# tricorder-teensy-mk-1_0.net
KiCad netlist of a schematic drawn in EAGLE
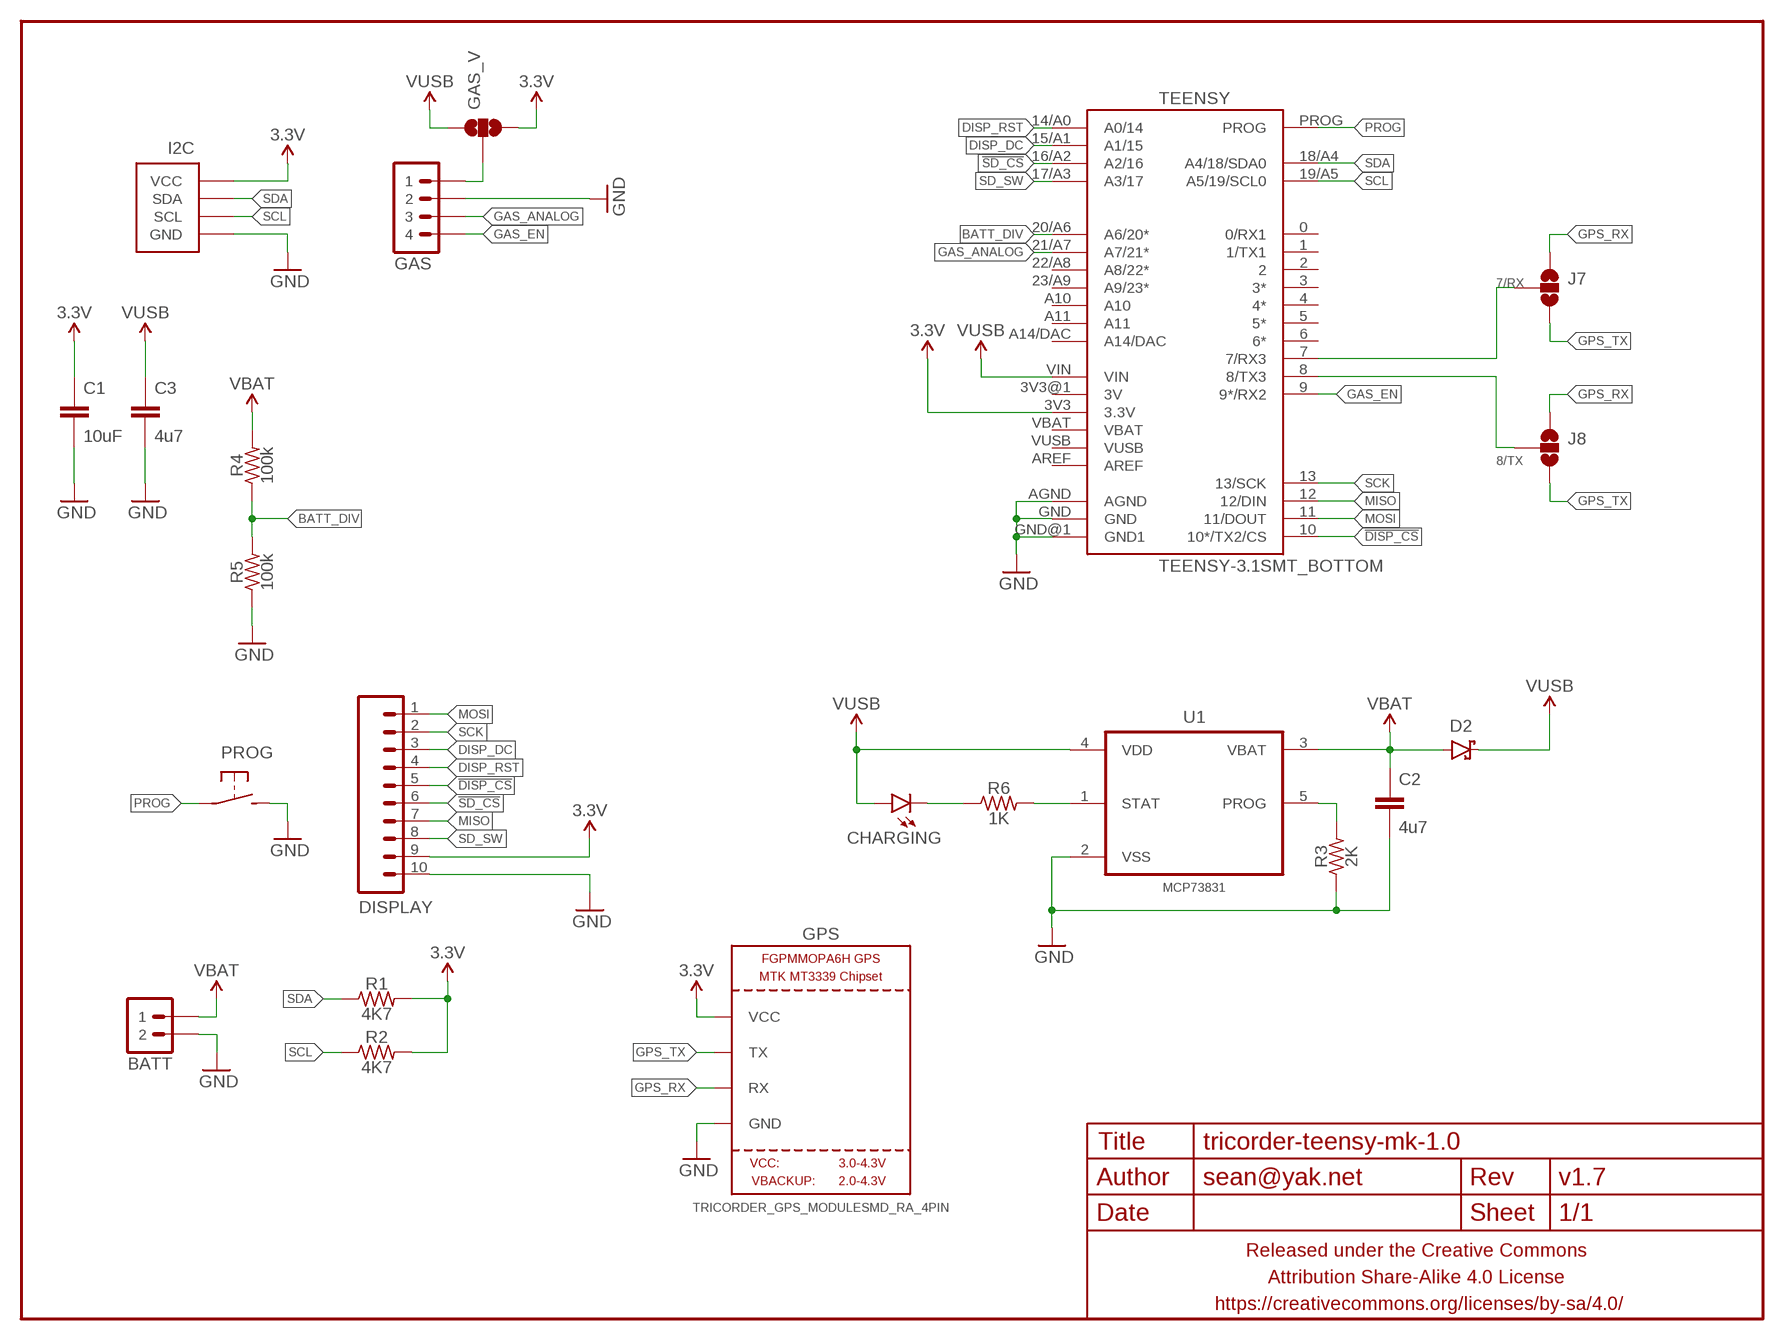
[diagram p0: schematic, sheet 1]

(export (version "E")
  (design (tool "Eeschema 10.0.6"))
  (components
    (comp (ref "BATT")
      (value "M02JST-2MM-SMT")
      (footprint "eagle-import:JST-2-SMD")
      (libsource (lib "eagle-import") (part "M02JST-2MM-SMT"))
    )
    (comp (ref "C1")
      (value "10uF")
      (footprint "eagle-import:C0805-TIGHTER")
      (libsource (lib "eagle-import") (part "CAPACITOR-CERAMICC0805-TIGHTER"))
    )
    (comp (ref "C2")
      (value "4u7")
      (footprint "eagle-import:C0603-TIGHTER")
      (libsource (lib "eagle-import") (part "CAPACITOR-CERAMICC0603-TIGHTER"))
    )
    (comp (ref "C3")
      (value "4u7")
      (footprint "eagle-import:C0603-TIGHTER")
      (libsource (lib "eagle-import") (part "CAPACITOR-CERAMICC0603-TIGHTER"))
    )
    (comp (ref "CHARGING")
      (value "LED0603-TIGHT")
      (footprint "eagle-import:LED-0603-TIGHT")
      (libsource (lib "eagle-import") (part "LED0603-TIGHT"))
    )
    (comp (ref "D2")
      (value "DIODE-SCHOTTKYSOD323")
      (footprint "eagle-import:SOD323-SCHOTTKY")
      (libsource (lib "eagle-import") (part "DIODE-SCHOTTKYSOD323"))
    )
    (comp (ref "DISPLAY")
      (value "M10SMD_RA_2MM")
      (footprint "eagle-import:1X10_SMD_RA_MALE")
      (libsource (lib "eagle-import") (part "M10SMD_RA_2MM"))
    )
    (comp (ref "FRAME1")
      (value "FRAME-LETTERNO_PACKAGE")
      (footprint "eagle-import:DUMMY")
      (fields (field (name "DESIGNER") "sean@yak.net") (field (name "VERSION") "v1.7"))
      (libsource (lib "eagle-import") (part "FRAME-LETTERNO_PACKAGE"))
    )
    (comp (ref "GAS")
      (value "M04SMD_RA_2MM")
      (footprint "eagle-import:1X04_SMD_RA_2MM")
      (libsource (lib "eagle-import") (part "M04SMD_RA_2MM"))
    )
    (comp (ref "GAS_V")
      (value "JUMPER-PAD-3-NOFULL_BOX_SILK")
      (footprint "eagle-import:PAD-JUMPER-3-NO_YES_SILK_FULL_BOX")
      (libsource (lib "eagle-import") (part "JUMPER-PAD-3-NOFULL_BOX_SILK"))
    )
    (comp (ref "GPS")
      (value "TRICORDER_GPS_MODULESMD_RA_4PIN")
      (footprint "eagle-import:TRICORDER_GPS_MODULE_RA_CONN_SMD_4PIN")
      (libsource (lib "eagle-import") (part "TRICORDER_GPS_MODULESMD_RA_4PIN"))
    )
    (comp (ref "I2C")
      (value "M04-I2CSMD_2MM_RA")
      (footprint "eagle-import:1X04_SMD_RA_2MM_I2C")
      (libsource (lib "eagle-import") (part "M04-I2CSMD_2MM_RA"))
    )
    (comp (ref "J7")
      (value "JUMPER-PAD-3-NOFULL_BOX_SILK")
      (footprint "eagle-import:PAD-JUMPER-3-NO_YES_SILK_FULL_BOX")
      (libsource (lib "eagle-import") (part "JUMPER-PAD-3-NOFULL_BOX_SILK"))
    )
    (comp (ref "J8")
      (value "JUMPER-PAD-3-NOFULL_BOX_SILK")
      (footprint "eagle-import:PAD-JUMPER-3-NO_YES_SILK_FULL_BOX")
      (libsource (lib "eagle-import") (part "JUMPER-PAD-3-NOFULL_BOX_SILK"))
    )
    (comp (ref "PROG")
      (value "SPST-NO-TACTCK-PTS840-GK")
      (footprint "eagle-import:TACTILE-SMD-CK-PTS840-GK")
      (libsource (lib "eagle-import") (part "SPST-NO-TACTCK-PTS840-GK"))
    )
    (comp (ref "R1")
      (value "4K7")
      (footprint "eagle-import:R0603-TIGHTER")
      (libsource (lib "eagle-import") (part "RESISTORR0603-TIGHTER"))
    )
    (comp (ref "R2")
      (value "4K7")
      (footprint "eagle-import:R0603-TIGHTER")
      (libsource (lib "eagle-import") (part "RESISTORR0603-TIGHTER"))
    )
    (comp (ref "R3")
      (value "2K")
      (footprint "eagle-import:R0603-TIGHTER")
      (libsource (lib "eagle-import") (part "RESISTORR0603-TIGHTER"))
    )
    (comp (ref "R4")
      (value "100k")
      (footprint "eagle-import:R0603-TIGHTER")
      (libsource (lib "eagle-import") (part "RESISTORR0603-TIGHTER"))
    )
    (comp (ref "R5")
      (value "100k")
      (footprint "eagle-import:R0603-TIGHTER")
      (libsource (lib "eagle-import") (part "RESISTORR0603-TIGHTER"))
    )
    (comp (ref "R6")
      (value "1K")
      (footprint "eagle-import:R0603-TIGHTER")
      (libsource (lib "eagle-import") (part "RESISTORR0603-TIGHTER"))
    )
    (comp (ref "TEENSY")
      (value "TEENSY-3.1SMT_BOTTOM")
      (footprint "eagle-import:TEENSY-3.1_SMT_BOTTOM")
      (libsource (lib "eagle-import") (part "TEENSY-3.1SMT_BOTTOM"))
    )
    (comp (ref "U1")
      (value "MCP73831")
      (footprint "eagle-import:SOT95P280X145-5N")
      (fields (field (name "MPN") "MCP73831T-2ACI/OT"))
      (libsource (lib "eagle-import") (part "MCP73831T-2ACI/OT"))
    )
  )
  (nets
    (net (code "1") (name "/7{slash}RX") (class "Default")
      (node (ref "J7") (pin "2") (pinfunction "2_2") (pintype "passive"))
      (node (ref "TEENSY") (pin "7") (pinfunction "7/RX3_7") (pintype "bidirectional"))
    )
    (net (code "2") (name "/8{slash}TX") (class "Default")
      (node (ref "J8") (pin "2") (pinfunction "2_2") (pintype "passive"))
      (node (ref "TEENSY") (pin "8") (pinfunction "8/TX3_8") (pintype "bidirectional"))
    )
    (net (code "3") (name "/~{DISP_CS}") (class "Default")
      (node (ref "DISPLAY") (pin "5") (pinfunction "5_5") (pintype "passive"))
      (node (ref "TEENSY") (pin "10") (pinfunction "10*/TX2/CS_10") (pintype "bidirectional"))
    )
    (net (code "4") (name "/~{SD_CS}") (class "Default")
      (node (ref "DISPLAY") (pin "6") (pinfunction "6_6") (pintype "passive"))
      (node (ref "TEENSY") (pin "16/A2") (pinfunction "A2/16_16/A2") (pintype "bidirectional"))
    )
    (net (code "5") (name "3.3V") (class "Default")
      (node (ref "C1") (pin "1") (pinfunction "1_1") (pintype "passive"))
      (node (ref "DISPLAY") (pin "9") (pinfunction "9_9") (pintype "passive"))
      (node (ref "GAS_V") (pin "3") (pinfunction "3_3") (pintype "passive"))
      (node (ref "GPS") (pin "VCC") (pinfunction "VCC_VCC") (pintype "bidirectional"))
      (node (ref "I2C") (pin "VCC") (pinfunction "VCC_VCC") (pintype "bidirectional"))
      (node (ref "R1") (pin "2") (pinfunction "2_2") (pintype "passive"))
      (node (ref "R2") (pin "2") (pinfunction "2_2") (pintype "passive"))
      (node (ref "TEENSY") (pin "3V3") (pinfunction "3.3V_3V3") (pintype "bidirectional"))
    )
    (net (code "6") (name "BATT_DIV") (class "Default")
      (node (ref "R4") (pin "1") (pinfunction "1_1") (pintype "passive"))
      (node (ref "R5") (pin "2") (pinfunction "2_2") (pintype "passive"))
      (node (ref "TEENSY") (pin "20/A6") (pinfunction "A6/20*_20/A6") (pintype "bidirectional"))
    )
    (net (code "7") (name "DISP_DC") (class "Default")
      (node (ref "DISPLAY") (pin "3") (pinfunction "3_3") (pintype "passive"))
      (node (ref "TEENSY") (pin "15/A1") (pinfunction "A1/15_15/A1") (pintype "bidirectional"))
    )
    (net (code "8") (name "DISP_RST") (class "Default")
      (node (ref "DISPLAY") (pin "4") (pinfunction "4_4") (pintype "passive"))
      (node (ref "TEENSY") (pin "14/A0") (pinfunction "A0/14_14/A0") (pintype "bidirectional"))
    )
    (net (code "9") (name "GAS_ANALOG") (class "Default")
      (node (ref "GAS") (pin "3") (pinfunction "3_3") (pintype "passive"))
      (node (ref "TEENSY") (pin "21/A7") (pinfunction "A7/21*_21/A7") (pintype "bidirectional"))
    )
    (net (code "10") (name "GAS_EN") (class "Default")
      (node (ref "GAS") (pin "4") (pinfunction "4_4") (pintype "passive"))
      (node (ref "TEENSY") (pin "9") (pinfunction "9*/RX2_9") (pintype "bidirectional"))
    )
    (net (code "11") (name "GND") (class "Default")
      (node (ref "BATT") (pin "1") (pinfunction "2_1") (pintype "passive"))
      (node (ref "C1") (pin "2") (pinfunction "2_2") (pintype "passive"))
      (node (ref "C2") (pin "2") (pinfunction "2_2") (pintype "passive"))
      (node (ref "C3") (pin "2") (pinfunction "2_2") (pintype "passive"))
      (node (ref "DISPLAY") (pin "10") (pinfunction "10_10") (pintype "passive"))
      (node (ref "GAS") (pin "2") (pinfunction "2_2") (pintype "passive"))
      (node (ref "GPS") (pin "GND") (pinfunction "GND_GND") (pintype "bidirectional"))
      (node (ref "I2C") (pin "GND") (pinfunction "GND_GND") (pintype "bidirectional"))
      (node (ref "PROG") (pin "3") (pinfunction "2_3") (pintype "passive"))
      (node (ref "PROG") (pin "4") (pinfunction "2_4") (pintype "passive"))
      (node (ref "R3") (pin "1") (pinfunction "1_1") (pintype "passive"))
      (node (ref "R5") (pin "1") (pinfunction "1_1") (pintype "passive"))
      (node (ref "TEENSY") (pin "AGND") (pinfunction "AGND_AGND") (pintype "bidirectional"))
      (node (ref "TEENSY") (pin "GND") (pinfunction "GND_GND") (pintype "bidirectional"))
      (node (ref "TEENSY") (pin "GND@1") (pinfunction "GND1_GND@1") (pintype "bidirectional"))
      (node (ref "U1") (pin "2") (pinfunction "VSS_2") (pintype "power_in"))
    )
    (net (code "12") (name "GPS_RX") (class "Default")
      (node (ref "GPS") (pin "RX") (pinfunction "RX_RX") (pintype "bidirectional"))
      (node (ref "J7") (pin "1") (pinfunction "1_1") (pintype "passive"))
      (node (ref "J8") (pin "1") (pinfunction "1_1") (pintype "passive"))
    )
    (net (code "13") (name "GPS_TX") (class "Default")
      (node (ref "GPS") (pin "TX") (pinfunction "TX_TX") (pintype "bidirectional"))
      (node (ref "J7") (pin "3") (pinfunction "3_3") (pintype "passive"))
      (node (ref "J8") (pin "3") (pinfunction "3_3") (pintype "passive"))
    )
    (net (code "14") (name "MISO") (class "Default")
      (node (ref "DISPLAY") (pin "7") (pinfunction "7_7") (pintype "passive"))
      (node (ref "TEENSY") (pin "12") (pinfunction "12/DIN_12") (pintype "bidirectional"))
    )
    (net (code "15") (name "MOSI") (class "Default")
      (node (ref "DISPLAY") (pin "1") (pinfunction "1_1") (pintype "passive"))
      (node (ref "TEENSY") (pin "11") (pinfunction "11/DOUT_11") (pintype "bidirectional"))
    )
    (net (code "16") (name "Net-(CHARGING-PadC)") (class "Default")
      (node (ref "CHARGING") (pin "C") (pinfunction "C_C") (pintype "passive"))
      (node (ref "R6") (pin "1") (pinfunction "1_1") (pintype "passive"))
    )
    (net (code "17") (name "Net-(GAS-Pad1)") (class "Default")
      (node (ref "GAS") (pin "1") (pinfunction "1_1") (pintype "passive"))
      (node (ref "GAS_V") (pin "2") (pinfunction "2_2") (pintype "passive"))
    )
    (net (code "18") (name "Net-(U1-PROG)") (class "Default")
      (node (ref "R3") (pin "2") (pinfunction "2_2") (pintype "passive"))
      (node (ref "U1") (pin "5") (pinfunction "PROG_5") (pintype "input"))
    )
    (net (code "19") (name "Net-(U1-STAT)") (class "Default")
      (node (ref "R6") (pin "2") (pinfunction "2_2") (pintype "passive"))
      (node (ref "U1") (pin "1") (pinfunction "STAT_1") (pintype "output"))
    )
    (net (code "20") (name "PROG") (class "Default")
      (node (ref "PROG") (pin "1") (pinfunction "1_1") (pintype "passive"))
      (node (ref "PROG") (pin "2") (pinfunction "1_2") (pintype "passive"))
      (node (ref "TEENSY") (pin "PROG") (pinfunction "PROG_PROG") (pintype "bidirectional"))
    )
    (net (code "21") (name "SCK") (class "Default")
      (node (ref "DISPLAY") (pin "2") (pinfunction "2_2") (pintype "passive"))
      (node (ref "TEENSY") (pin "13") (pinfunction "13/SCK_13") (pintype "bidirectional"))
    )
    (net (code "22") (name "SCL") (class "Default")
      (node (ref "I2C") (pin "SCL") (pinfunction "SCL_SCL") (pintype "bidirectional"))
      (node (ref "R2") (pin "1") (pinfunction "1_1") (pintype "passive"))
      (node (ref "TEENSY") (pin "19/A5") (pinfunction "A5/19/SCL0_19/A5") (pintype "bidirectional"))
    )
    (net (code "23") (name "SDA") (class "Default")
      (node (ref "I2C") (pin "SDA") (pinfunction "SDA_SDA") (pintype "bidirectional"))
      (node (ref "R1") (pin "1") (pinfunction "1_1") (pintype "passive"))
      (node (ref "TEENSY") (pin "18/A4") (pinfunction "A4/18/SDA0_18/A4") (pintype "bidirectional"))
    )
    (net (code "24") (name "SD_SW") (class "Default")
      (node (ref "DISPLAY") (pin "8") (pinfunction "8_8") (pintype "passive"))
      (node (ref "TEENSY") (pin "17/A3") (pinfunction "A3/17_17/A3") (pintype "bidirectional"))
    )
    (net (code "25") (name "VBAT") (class "Default")
      (node (ref "BATT") (pin "2") (pinfunction "1_2") (pintype "passive"))
      (node (ref "C2") (pin "1") (pinfunction "1_1") (pintype "passive"))
      (node (ref "D2") (pin "A") (pinfunction "A_A") (pintype "passive"))
      (node (ref "R4") (pin "2") (pinfunction "2_2") (pintype "passive"))
      (node (ref "U1") (pin "3") (pinfunction "VBAT_3") (pintype "output"))
    )
    (net (code "26") (name "VUSB") (class "Default")
      (node (ref "C3") (pin "1") (pinfunction "1_1") (pintype "passive"))
      (node (ref "CHARGING") (pin "A") (pinfunction "A_A") (pintype "passive"))
      (node (ref "D2") (pin "C") (pinfunction "C_C") (pintype "passive"))
      (node (ref "GAS_V") (pin "1") (pinfunction "1_1") (pintype "passive"))
      (node (ref "TEENSY") (pin "VIN") (pinfunction "VIN_VIN") (pintype "bidirectional"))
      (node (ref "U1") (pin "4") (pinfunction "VDD_4") (pintype "power_in"))
    )
    (net (code "27") (name "unconnected-(TEENSY-0{slash}RX1-Pad0)") (class "Default")
      (node (ref "TEENSY") (pin "0") (pinfunction "0/RX1_0") (pintype "bidirectional"))
    )
    (net (code "28") (name "unconnected-(TEENSY-1{slash}TX1-Pad1)") (class "Default")
      (node (ref "TEENSY") (pin "1") (pinfunction "1/TX1_1") (pintype "bidirectional"))
    )
    (net (code "29") (name "unconnected-(TEENSY-3*-Pad3)") (class "Default")
      (node (ref "TEENSY") (pin "3") (pinfunction "3*_3") (pintype "bidirectional"))
    )
    (net (code "30") (name "unconnected-(TEENSY-3V-Pad3V3@1)") (class "Default")
      (node (ref "TEENSY") (pin "3V3@1") (pinfunction "3V_3V3@1") (pintype "bidirectional"))
    )
    (net (code "31") (name "unconnected-(TEENSY-4*-Pad4)") (class "Default")
      (node (ref "TEENSY") (pin "4") (pinfunction "4*_4") (pintype "bidirectional"))
    )
    (net (code "32") (name "unconnected-(TEENSY-5*-Pad5)") (class "Default")
      (node (ref "TEENSY") (pin "5") (pinfunction "5*_5") (pintype "bidirectional"))
    )
    (net (code "33") (name "unconnected-(TEENSY-6*-Pad6)") (class "Default")
      (node (ref "TEENSY") (pin "6") (pinfunction "6*_6") (pintype "bidirectional"))
    )
    (net (code "34") (name "unconnected-(TEENSY-A8{slash}22*-Pad22{slash}A8)") (class "Default")
      (node (ref "TEENSY") (pin "22/A8") (pinfunction "A8/22*_22/A8") (pintype "bidirectional"))
    )
    (net (code "35") (name "unconnected-(TEENSY-A9{slash}23*-Pad23{slash}A9)") (class "Default")
      (node (ref "TEENSY") (pin "23/A9") (pinfunction "A9/23*_23/A9") (pintype "bidirectional"))
    )
    (net (code "36") (name "unconnected-(TEENSY-Pad2)") (class "Default")
      (node (ref "TEENSY") (pin "2") (pinfunction "2_2") (pintype "bidirectional"))
    )
    (net (code "37") (name "unconnected-(TEENSY-PadA10)") (class "Default")
      (node (ref "TEENSY") (pin "A10") (pinfunction "A10_A10") (pintype "bidirectional"))
    )
    (net (code "38") (name "unconnected-(TEENSY-PadA11)") (class "Default")
      (node (ref "TEENSY") (pin "A11") (pinfunction "A11_A11") (pintype "bidirectional"))
    )
    (net (code "39") (name "unconnected-(TEENSY-PadA14{slash}DAC)") (class "Default")
      (node (ref "TEENSY") (pin "A14/DAC") (pinfunction "A14/DAC_A14/DAC") (pintype "bidirectional"))
    )
    (net (code "40") (name "unconnected-(TEENSY-PadAREF)") (class "Default")
      (node (ref "TEENSY") (pin "AREF") (pinfunction "AREF_AREF") (pintype "bidirectional"))
    )
    (net (code "41") (name "unconnected-(TEENSY-PadVBAT)") (class "Default")
      (node (ref "TEENSY") (pin "VBAT") (pinfunction "VBAT_VBAT") (pintype "bidirectional"))
    )
    (net (code "42") (name "unconnected-(TEENSY-PadVUSB)") (class "Default")
      (node (ref "TEENSY") (pin "VUSB") (pinfunction "VUSB_VUSB") (pintype "bidirectional"))
    )
  )
)
